# Power_Cell_Lipo_Charger_Booster_try2.net
KiCad netlist of a schematic drawn in EAGLE
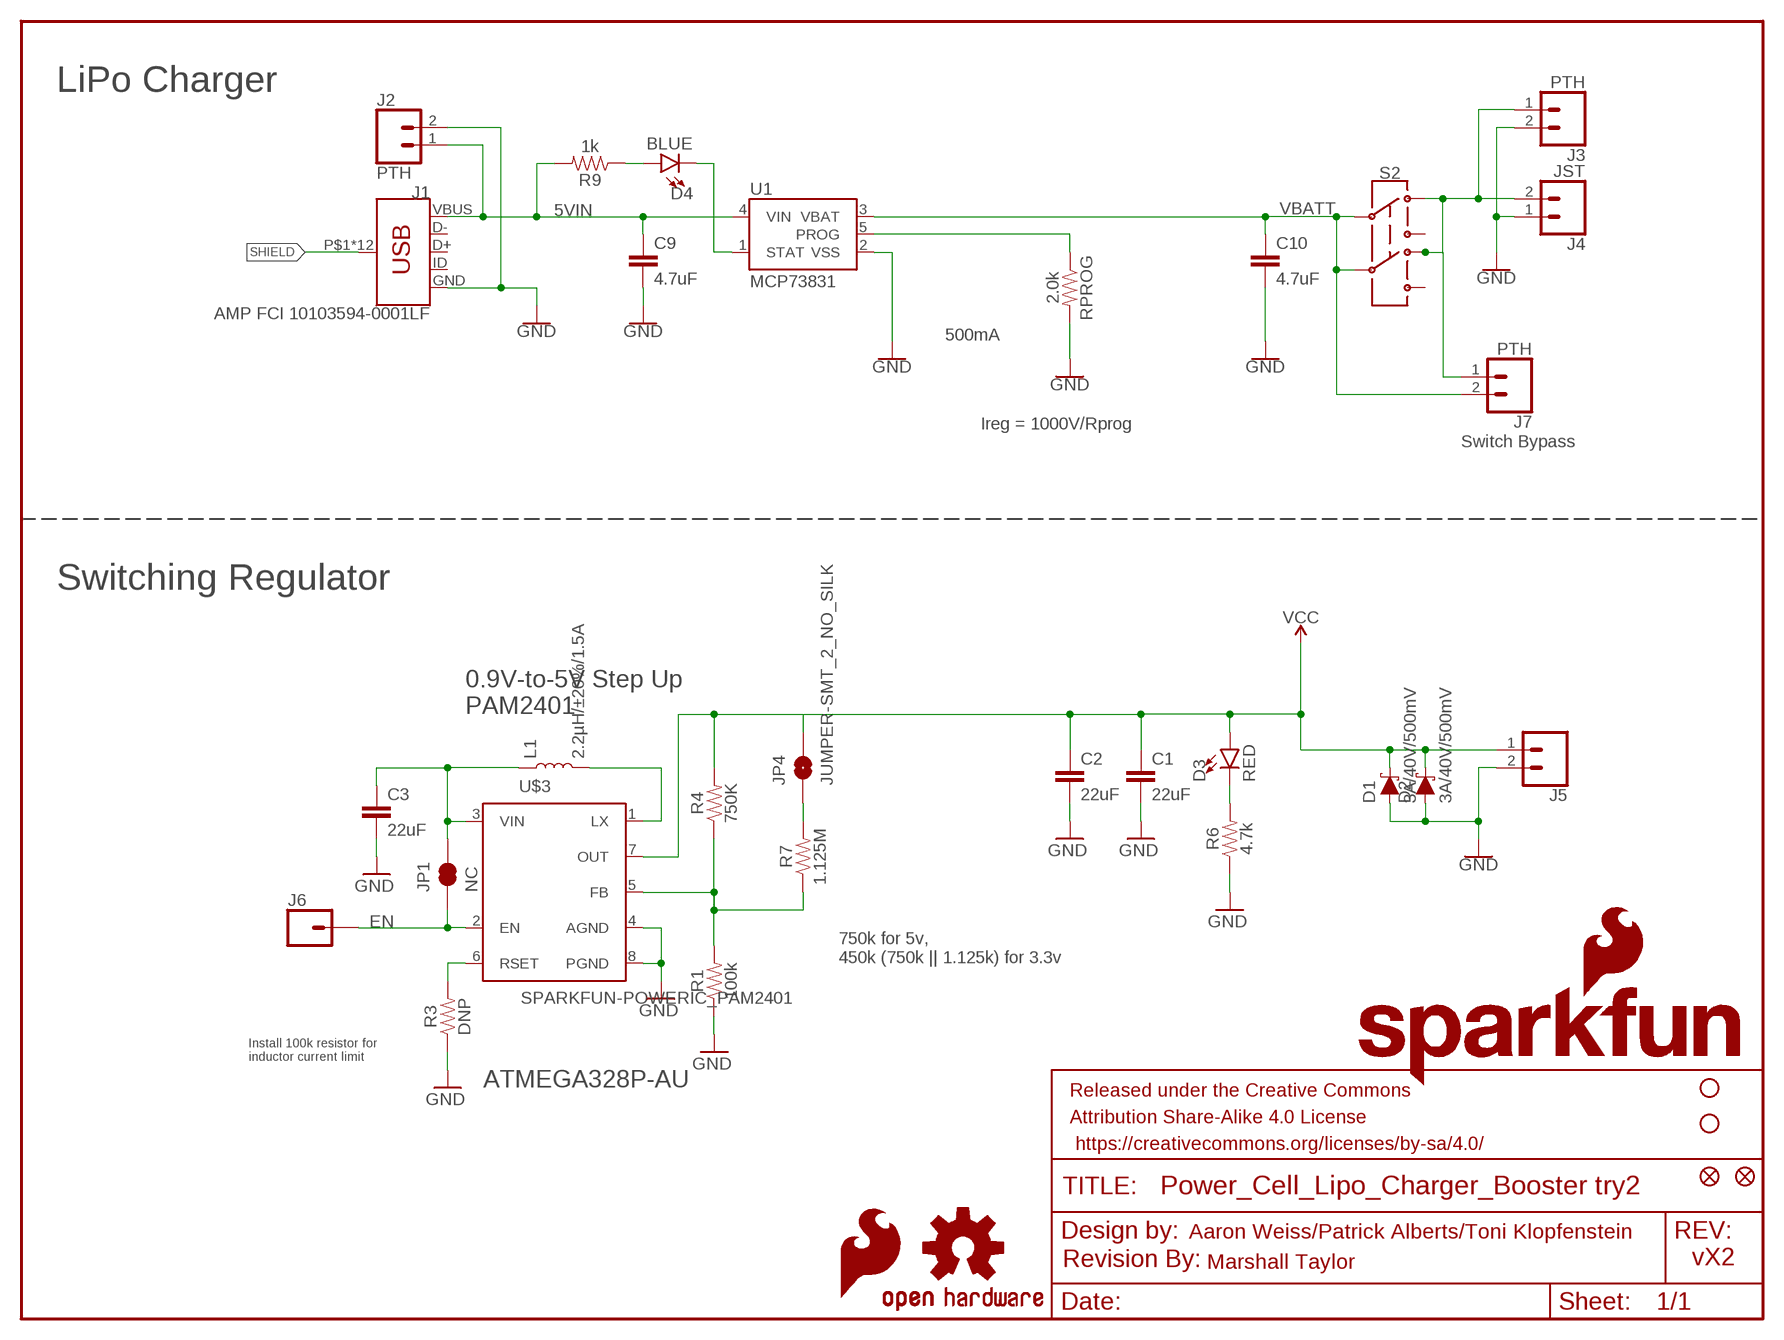
[diagram p0: schematic, sheet 1]

(export (version "E")
  (design (tool "Eeschema 10.0.6"))
  (components
    (comp (ref "C1")
      (value "22uF")
      (footprint "eagle-import:0805")
      (libsource (lib "eagle-import") (part "22UF-0805-6.3V-20%"))
    )
    (comp (ref "C2")
      (value "22uF")
      (footprint "eagle-import:0805")
      (libsource (lib "eagle-import") (part "22UF-0805-6.3V-20%"))
    )
    (comp (ref "C3")
      (value "22uF")
      (footprint "eagle-import:0805")
      (libsource (lib "eagle-import") (part "22UF-0805-6.3V-20%"))
    )
    (comp (ref "C9")
      (value "4.7uF")
      (footprint "eagle-import:0603")
      (libsource (lib "eagle-import") (part "4.7UF0603"))
    )
    (comp (ref "C10")
      (value "4.7uF")
      (footprint "eagle-import:0603")
      (libsource (lib "eagle-import") (part "4.7UF0603"))
    )
    (comp (ref "D1")
      (value "3A/40V/500mV")
      (footprint "eagle-import:SMA-DIODE")
      (libsource (lib "eagle-import") (part "DIODE-SCHOTTKY-B340A"))
    )
    (comp (ref "D2")
      (value "3A/40V/500mV")
      (footprint "eagle-import:SMA-DIODE")
      (libsource (lib "eagle-import") (part "DIODE-SCHOTTKY-B340A"))
    )
    (comp (ref "D3")
      (value "RED")
      (footprint "eagle-import:LED-0603")
      (libsource (lib "eagle-import") (part "LED-RED0603"))
    )
    (comp (ref "D4")
      (value "BLUE")
      (footprint "eagle-import:LED-0603")
      (libsource (lib "eagle-import") (part "LED-BLUE0603"))
    )
    (comp (ref "FRAME1")
      (value "FRAME-LETTER")
      (footprint "eagle-import:CREATIVE_COMMONS")
      (libsource (lib "eagle-import") (part "FRAME-LETTER"))
    )
    (comp (ref "J1")
      (value "AMP FCI 10103594-0001LF")
      (footprint "eagle-import:USB-MICROB-PTH")
      (libsource (lib "eagle-import") (part "USB_MICRO-B_HALF_PTH"))
    )
    (comp (ref "J2")
      (value "PTH")
      (footprint "eagle-import:1X02")
      (libsource (lib "eagle-import") (part "CONN_02"))
    )
    (comp (ref "J3")
      (value "PTH")
      (footprint "eagle-import:1X02")
      (libsource (lib "eagle-import") (part "CONN_02"))
    )
    (comp (ref "J4")
      (value "JST")
      (footprint "eagle-import:JST-2-SMD")
      (libsource (lib "eagle-import") (part "CONN_02-JST-2MM-SMT"))
    )
    (comp (ref "J5")
      (value "CONN_02")
      (footprint "eagle-import:1X02")
      (libsource (lib "eagle-import") (part "CONN_02"))
    )
    (comp (ref "J6")
      (value "CONN_01")
      (footprint "eagle-import:1X01")
      (libsource (lib "eagle-import") (part "CONN_01"))
    )
    (comp (ref "J7")
      (value "PTH")
      (footprint "eagle-import:1X02")
      (libsource (lib "eagle-import") (part "CONN_02"))
    )
    (comp (ref "JP1")
      (value "NC")
      (footprint "eagle-import:SMT-JUMPER_2_NC_TRACE_NO-SILK")
      (libsource (lib "eagle-import") (part "JUMPER-SMT_2_NC_TRACE_NO-SILK"))
    )
    (comp (ref "JP2")
      (value "FIDUCIAL1X2")
      (footprint "eagle-import:FIDUCIAL-1X2")
      (libsource (lib "eagle-import") (part "FIDUCIAL1X2"))
    )
    (comp (ref "JP3")
      (value "SFE_LOGO_NAME_FLAME.1_INCH")
      (footprint "eagle-import:SFE_LOGO_NAME_FLAME_.1")
      (libsource (lib "eagle-import") (part "SFE_LOGO_NAME_FLAME.1_INCH"))
    )
    (comp (ref "JP4")
      (value "JUMPER-SMT_2_NO_SILK")
      (footprint "eagle-import:SMT-JUMPER_2_NO_SILK")
      (libsource (lib "eagle-import") (part "JUMPER-SMT_2_NO_SILK"))
    )
    (comp (ref "JP6")
      (value "STAND-OFF")
      (footprint "eagle-import:STAND-OFF")
      (libsource (lib "eagle-import") (part "STAND-OFF"))
    )
    (comp (ref "JP7")
      (value "STAND-OFF")
      (footprint "eagle-import:STAND-OFF")
      (libsource (lib "eagle-import") (part "STAND-OFF"))
    )
    (comp (ref "JP16")
      (value "FIDUCIAL1X2")
      (footprint "eagle-import:FIDUCIAL-1X2")
      (libsource (lib "eagle-import") (part "FIDUCIAL1X2"))
    )
    (comp (ref "L1")
      (value "2.2µH/±20%/1.5A")
      (footprint "eagle-import:INDUCTOR_2.2UHCOPY")
      (libsource (lib "eagle-import") (part "INDUCTORCOPY-VLF4012AT-2.2UH"))
    )
    (comp (ref "LOGO1")
      (value "SFE_LOGO_FLAME.1_INCH")
      (footprint "eagle-import:SFE_LOGO_FLAME_.1")
      (libsource (lib "eagle-import") (part "SFE_LOGO_FLAME.1_INCH"))
    )
    (comp (ref "R1")
      (value "100k")
      (footprint "eagle-import:0603")
      (libsource (lib "eagle-import") (part "100KOHM-0603-1/10W-1%"))
    )
    (comp (ref "R3")
      (value "DNP")
      (footprint "eagle-import:0603")
      (libsource (lib "eagle-import") (part "100KOHM-0603-1/10W-1%"))
    )
    (comp (ref "R4")
      (value "750K")
      (footprint "eagle-import:0603")
      (libsource (lib "eagle-import") (part "750OHM-0603-1/10W-1%"))
    )
    (comp (ref "R6")
      (value "4.7k")
      (footprint "eagle-import:0603")
      (libsource (lib "eagle-import") (part "4.7KOHM-0603-1/10W-1%"))
    )
    (comp (ref "R7")
      (value "1.125M")
      (footprint "eagle-import:0603")
      (libsource (lib "eagle-import") (part "750OHM-0603-1/10W-1%"))
    )
    (comp (ref "R9")
      (value "1k")
      (footprint "eagle-import:0603")
      (libsource (lib "eagle-import") (part "1KOHM-0603-1/10W-1%"))
    )
    (comp (ref "RPROG")
      (value "2.0k")
      (footprint "eagle-import:0603")
      (libsource (lib "eagle-import") (part "2.0KOHM-0603-1/10W-5%"))
    )
    (comp (ref "S2")
      (value "SWITCH-DPDT-SMD-AYZ0202")
      (footprint "eagle-import:SWITCH_DPDT_SMD_AYZ0202")
      (libsource (lib "eagle-import") (part "SWITCH-DPDT-SMD-AYZ0202"))
    )
    (comp (ref "U$1")
      (value "OSHW-LOGOS")
      (footprint "eagle-import:OSHW-LOGO-S")
      (libsource (lib "eagle-import") (part "OSHW-LOGOS"))
    )
    (comp (ref "U$2")
      (value "REVISION")
      (footprint "eagle-import:REVISION")
      (libsource (lib "eagle-import") (part "REVISION"))
    )
    (comp (ref "U$3")
      (value "SPARKFUN-POWERIC_PAM2401")
      (footprint "eagle-import:SPARKFUN-POWERIC_MSOP8")
      (libsource (lib "eagle-import") (part "SPARKFUN-POWERIC_PAM2401"))
    )
    (comp (ref "U1")
      (value "MCP73831")
      (footprint "eagle-import:SOT23-5")
      (libsource (lib "eagle-import") (part "MCP73831"))
    )
  )
  (nets
    (net (code "1") (name "/5VIN") (class "Default")
      (node (ref "C9") (pin "1") (pinfunction "1_1") (pintype "passive"))
      (node (ref "J1") (pin "VBUS") (pinfunction "VBUS_VBUS") (pintype "power_in"))
      (node (ref "J2") (pin "1") (pinfunction "1_1") (pintype "passive"))
      (node (ref "R9") (pin "2") (pinfunction "2_2") (pintype "passive"))
      (node (ref "U1") (pin "4") (pinfunction "VIN_4") (pintype "power_in"))
    )
    (net (code "2") (name "/EN") (class "Default")
      (node (ref "J6") (pin "1") (pinfunction "1_1") (pintype "passive"))
      (node (ref "JP1") (pin "1") (pinfunction "1_1") (pintype "passive"))
      (node (ref "U$3") (pin "2") (pinfunction "EN_2") (pintype "bidirectional"))
    )
    (net (code "3") (name "/VBATT") (class "Default")
      (node (ref "C10") (pin "1") (pinfunction "1_1") (pintype "passive"))
      (node (ref "C3") (pin "1") (pinfunction "1_1") (pintype "passive"))
      (node (ref "J7") (pin "2") (pinfunction "2_2") (pintype "passive"))
      (node (ref "JP1") (pin "2") (pinfunction "2_2") (pintype "passive"))
      (node (ref "L1") (pin "P$1") (pinfunction "1_P$1") (pintype "passive"))
      (node (ref "S2") (pin "2") (pinfunction "2_2") (pintype "bidirectional"))
      (node (ref "S2") (pin "5") (pinfunction "5_5") (pintype "bidirectional"))
      (node (ref "U$3") (pin "3") (pinfunction "VIN_3") (pintype "bidirectional"))
      (node (ref "U1") (pin "3") (pinfunction "VBAT_3") (pintype "power_in"))
    )
    (net (code "4") (name "GND") (class "Default")
      (node (ref "C1") (pin "2") (pinfunction "2_2") (pintype "passive"))
      (node (ref "C10") (pin "2") (pinfunction "2_2") (pintype "passive"))
      (node (ref "C2") (pin "2") (pinfunction "2_2") (pintype "passive"))
      (node (ref "C3") (pin "2") (pinfunction "2_2") (pintype "passive"))
      (node (ref "C9") (pin "2") (pinfunction "2_2") (pintype "passive"))
      (node (ref "D1") (pin "A") (pinfunction "A_A") (pintype "passive"))
      (node (ref "D2") (pin "A") (pinfunction "A_A") (pintype "passive"))
      (node (ref "J1") (pin "GND") (pinfunction "GND_GND") (pintype "power_in"))
      (node (ref "J2") (pin "2") (pinfunction "2_2") (pintype "passive"))
      (node (ref "J3") (pin "2") (pinfunction "2_2") (pintype "passive"))
      (node (ref "J4") (pin "1") (pinfunction "2_1") (pintype "passive"))
      (node (ref "J5") (pin "2") (pinfunction "2_2") (pintype "passive"))
      (node (ref "R1") (pin "1") (pinfunction "1_1") (pintype "passive"))
      (node (ref "R3") (pin "1") (pinfunction "1_1") (pintype "passive"))
      (node (ref "R6") (pin "1") (pinfunction "1_1") (pintype "passive"))
      (node (ref "RPROG") (pin "2") (pinfunction "2_2") (pintype "passive"))
      (node (ref "U$3") (pin "4") (pinfunction "AGND_4") (pintype "bidirectional"))
      (node (ref "U$3") (pin "8") (pinfunction "PGND_8") (pintype "bidirectional"))
      (node (ref "U1") (pin "2") (pinfunction "VSS_2") (pintype "power_in"))
    )
    (net (code "5") (name "Net-(D3-PadC)") (class "Default")
      (node (ref "D3") (pin "C") (pinfunction "C_C") (pintype "passive"))
      (node (ref "R6") (pin "2") (pinfunction "2_2") (pintype "passive"))
    )
    (net (code "6") (name "Net-(D4-PadA)") (class "Default")
      (node (ref "D4") (pin "A") (pinfunction "A_A") (pintype "passive"))
      (node (ref "R9") (pin "1") (pinfunction "1_1") (pintype "passive"))
    )
    (net (code "7") (name "Net-(J4-1)") (class "Default")
      (node (ref "J3") (pin "1") (pinfunction "1_1") (pintype "passive"))
      (node (ref "J4") (pin "2") (pinfunction "1_2") (pintype "passive"))
      (node (ref "J7") (pin "1") (pinfunction "1_1") (pintype "passive"))
      (node (ref "S2") (pin "1") (pinfunction "1_1") (pintype "bidirectional"))
      (node (ref "S2") (pin "4") (pinfunction "4_4") (pintype "bidirectional"))
    )
    (net (code "8") (name "Net-(JP4-Pad1)") (class "Default")
      (node (ref "JP4") (pin "1") (pinfunction "1_1") (pintype "passive"))
      (node (ref "R7") (pin "2") (pinfunction "2_2") (pintype "passive"))
    )
    (net (code "9") (name "Net-(L1-2)") (class "Default")
      (node (ref "L1") (pin "P$2") (pinfunction "2_P$2") (pintype "passive"))
      (node (ref "U$3") (pin "1") (pinfunction "LX_1") (pintype "bidirectional"))
    )
    (net (code "10") (name "Net-(U$3-FB)") (class "Default")
      (node (ref "R1") (pin "2") (pinfunction "2_2") (pintype "passive"))
      (node (ref "R4") (pin "1") (pinfunction "1_1") (pintype "passive"))
      (node (ref "R7") (pin "1") (pinfunction "1_1") (pintype "passive"))
      (node (ref "U$3") (pin "5") (pinfunction "FB_5") (pintype "bidirectional"))
    )
    (net (code "11") (name "Net-(U$3-RSET)") (class "Default")
      (node (ref "R3") (pin "2") (pinfunction "2_2") (pintype "passive"))
      (node (ref "U$3") (pin "6") (pinfunction "RSET_6") (pintype "bidirectional"))
    )
    (net (code "12") (name "Net-(U1-PROG)") (class "Default")
      (node (ref "RPROG") (pin "1") (pinfunction "1_1") (pintype "passive"))
      (node (ref "U1") (pin "5") (pinfunction "PROG_5") (pintype "input"))
    )
    (net (code "13") (name "Net-(U1-STAT)") (class "Default")
      (node (ref "D4") (pin "C") (pinfunction "C_C") (pintype "passive"))
      (node (ref "U1") (pin "1") (pinfunction "STAT_1") (pintype "output"))
    )
    (net (code "14") (name "SHIELD") (class "Default")
      (node (ref "J1") (pin "P$1") (pinfunction "SHIELD_P$1") (pintype "bidirectional"))
      (node (ref "J1") (pin "P$10") (pinfunction "SHIELD_P$10") (pintype "bidirectional"))
      (node (ref "J1") (pin "P$12") (pinfunction "SHIELD_P$12") (pintype "bidirectional"))
      (node (ref "J1") (pin "P$2") (pinfunction "SHIELD_P$2") (pintype "bidirectional"))
      (node (ref "J1") (pin "P$3") (pinfunction "SHIELD_P$3") (pintype "bidirectional"))
      (node (ref "J1") (pin "P$4") (pinfunction "SHIELD_P$4") (pintype "bidirectional"))
      (node (ref "J1") (pin "P$6") (pinfunction "SHIELD_P$6") (pintype "bidirectional"))
      (node (ref "J1") (pin "P$8") (pinfunction "SHIELD_P$8") (pintype "bidirectional"))
      (node (ref "J1") (pin "SHEILD2") (pinfunction "SHIELD_SHEILD2") (pintype "bidirectional"))
      (node (ref "J1") (pin "SHIELD") (pinfunction "SHIELD_SHIELD") (pintype "bidirectional"))
      (node (ref "J1") (pin "SHIELD3") (pinfunction "SHIELD_SHIELD3") (pintype "bidirectional"))
      (node (ref "J1") (pin "SHIELD4") (pinfunction "SHIELD_SHIELD4") (pintype "bidirectional"))
    )
    (net (code "15") (name "VCC") (class "Default")
      (node (ref "C1") (pin "1") (pinfunction "1_1") (pintype "passive"))
      (node (ref "C2") (pin "1") (pinfunction "1_1") (pintype "passive"))
      (node (ref "D1") (pin "C") (pinfunction "C_C") (pintype "passive"))
      (node (ref "D2") (pin "C") (pinfunction "C_C") (pintype "passive"))
      (node (ref "D3") (pin "A") (pinfunction "A_A") (pintype "passive"))
      (node (ref "J5") (pin "1") (pinfunction "1_1") (pintype "passive"))
      (node (ref "JP4") (pin "2") (pinfunction "2_2") (pintype "passive"))
      (node (ref "R4") (pin "2") (pinfunction "2_2") (pintype "passive"))
      (node (ref "U$3") (pin "7") (pinfunction "OUT_7") (pintype "bidirectional"))
    )
    (net (code "16") (name "unconnected-(J1-PadD+)") (class "Default")
      (node (ref "J1") (pin "D+") (pinfunction "D+_D+") (pintype "bidirectional"))
    )
    (net (code "17") (name "unconnected-(J1-PadD-)") (class "Default")
      (node (ref "J1") (pin "D-") (pinfunction "D-_D-") (pintype "bidirectional"))
    )
    (net (code "18") (name "unconnected-(J1-PadID)") (class "Default")
      (node (ref "J1") (pin "ID") (pinfunction "ID_ID") (pintype "bidirectional"))
    )
    (net (code "19") (name "unconnected-(S2-Pad3)") (class "Default")
      (node (ref "S2") (pin "3") (pinfunction "3_3") (pintype "bidirectional"))
    )
    (net (code "20") (name "unconnected-(S2-Pad6)") (class "Default")
      (node (ref "S2") (pin "6") (pinfunction "6_6") (pintype "bidirectional"))
    )
  )
)
